# SCH_LED-Chaser_2025-12-03.net
KiCad netlist of a schematic drawn in EasyEDA
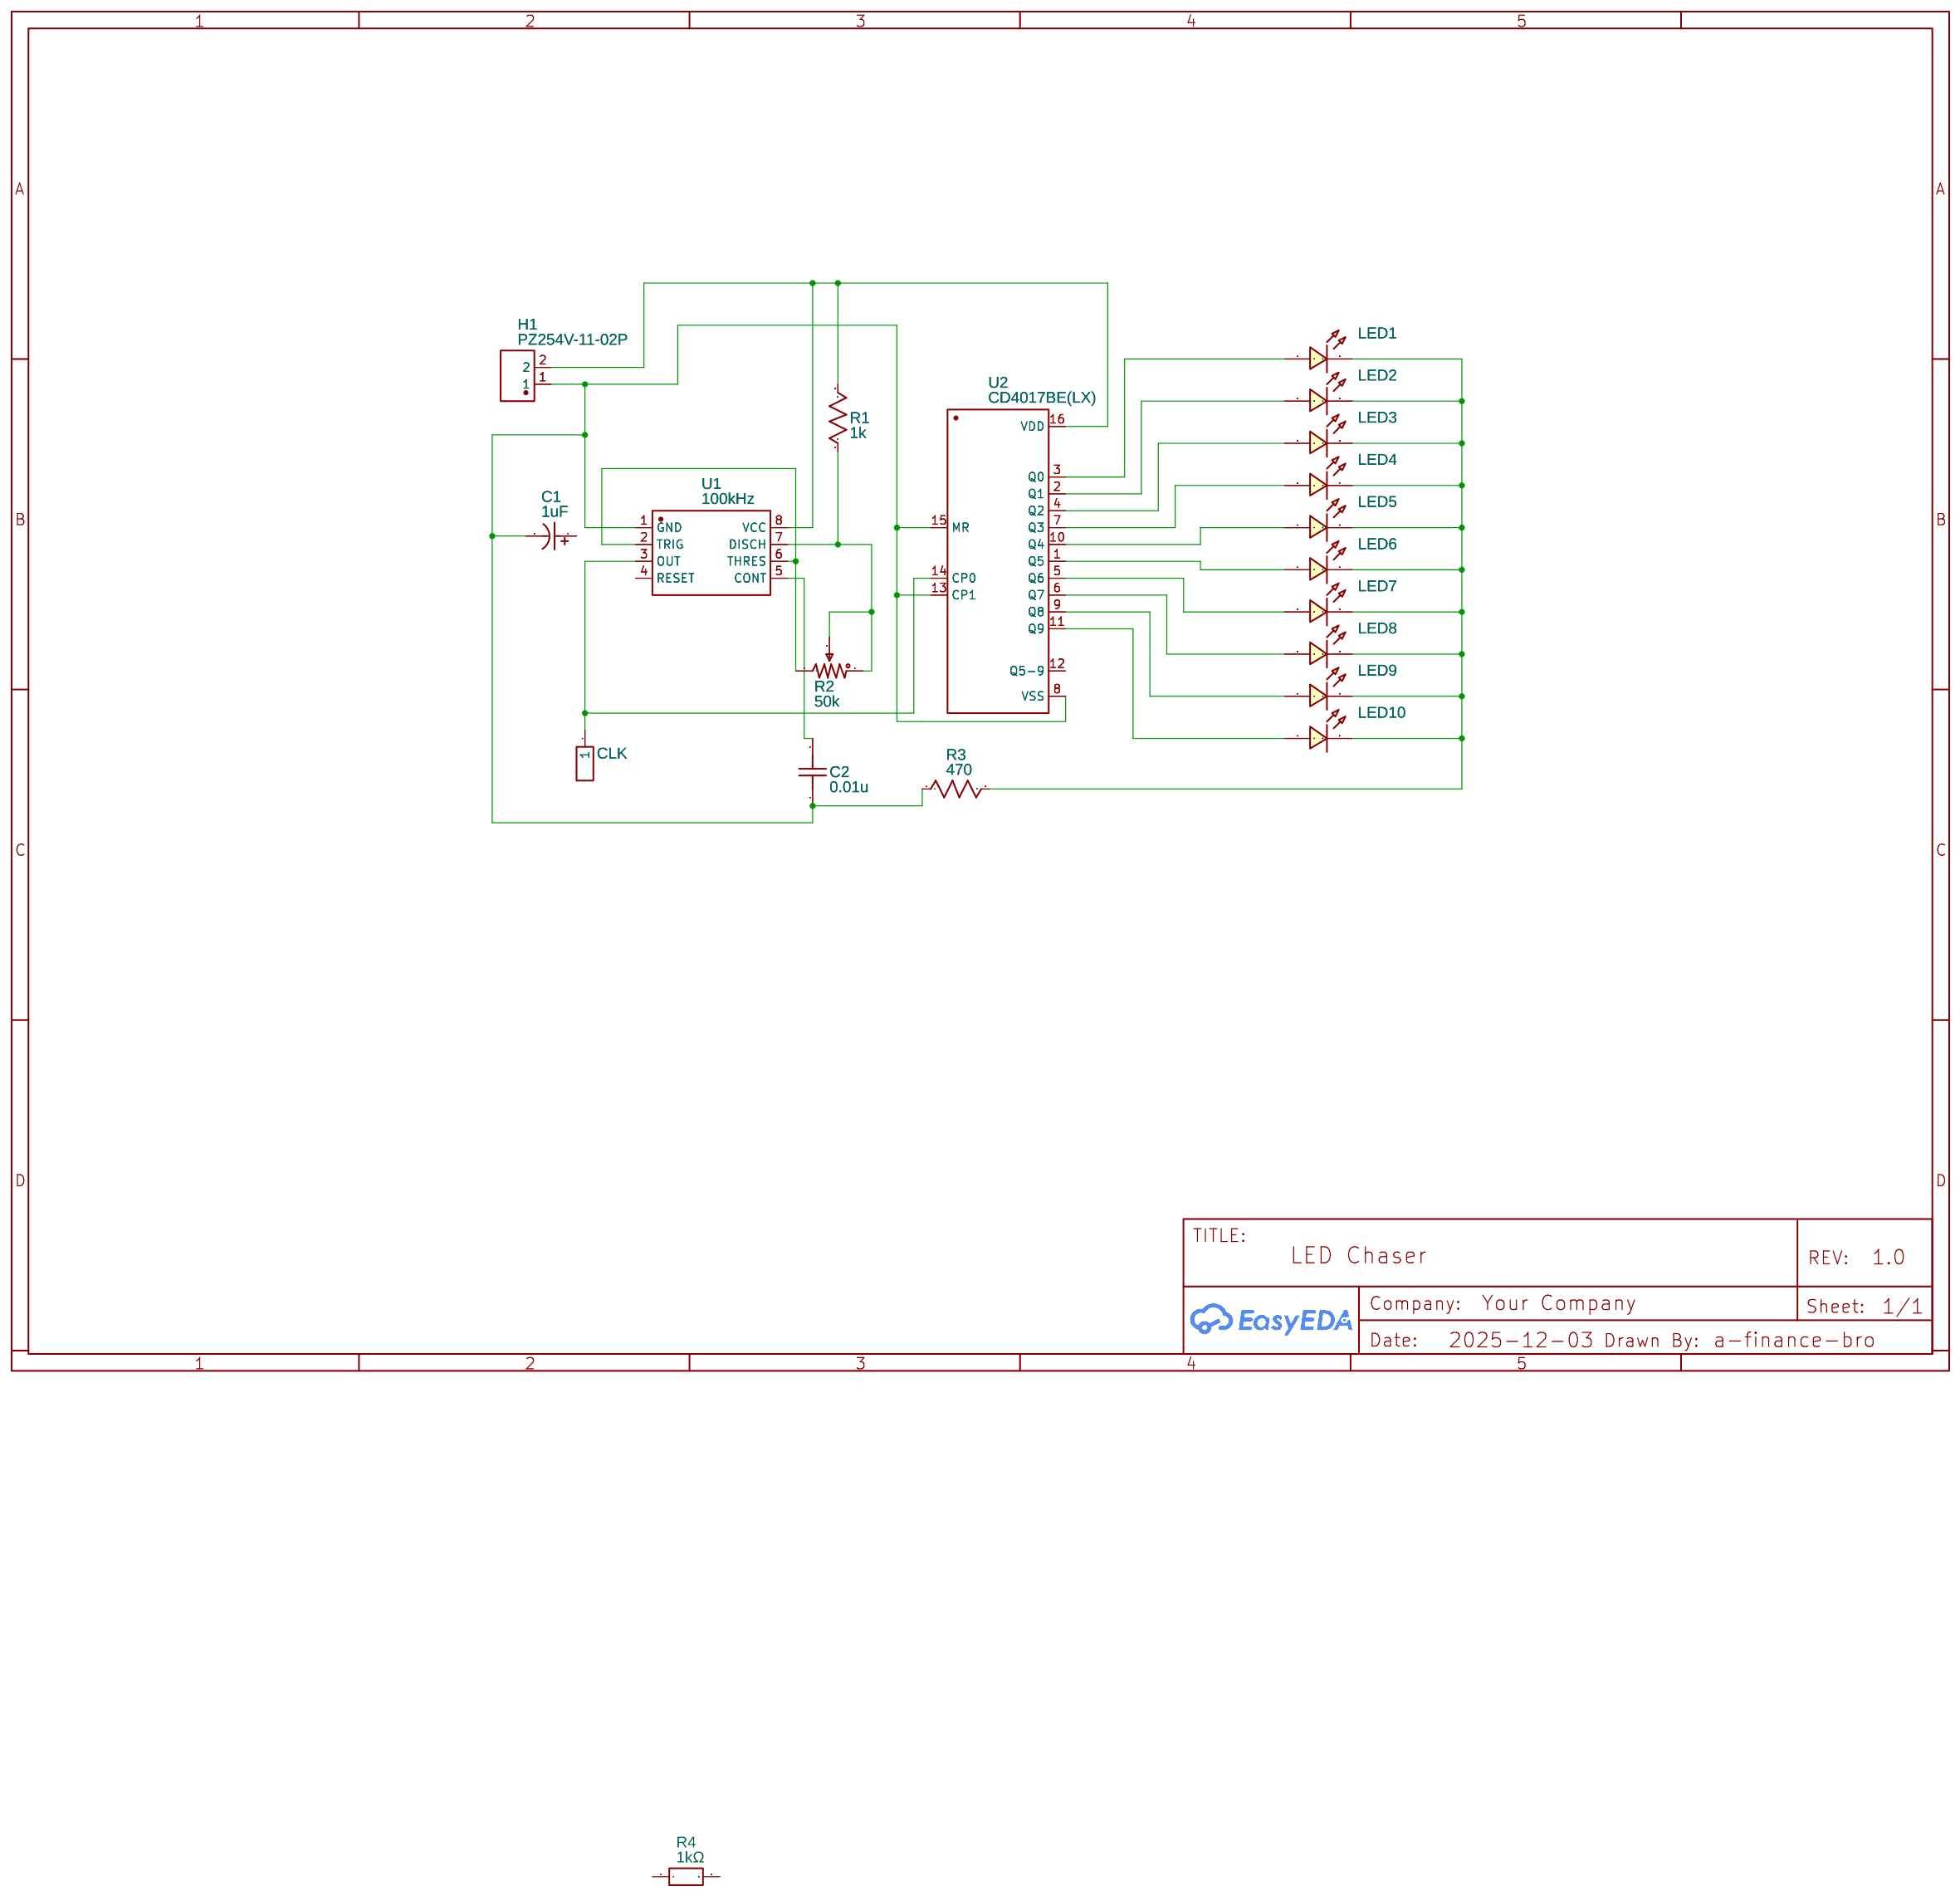
[diagram p0: schematic sheet]

(export (version "E")
  (design (tool "Eeschema 10.0.6"))
  (components
    (comp (ref "C1")
      (value "1uF")
      (fields (field (name "Manufacturer Part") "KF010M050C110A") (field (name "Manufacturer") "CapXon(丰宾)"))
      (libsource (lib "") (part "KF010M050C110A"))
    )
    (comp (ref "C2") (value "0.01u") (libsource (lib "") (part "C_0603_US")))
    (comp (ref "CLK") (value "HDR-M-2.54_1x1") (libsource (lib "") (part "HDR-M-2.54_1x1")))
    (comp (ref "H1")
      (value "PZ254V-11-02P")
      (fields (field (name "Manufacturer") "XFCN(兴飞)"))
      (libsource (lib "") (part "PZ254V-11-02P"))
    )
    (comp (ref "LED1")
      (value "LED-0603_R")
      (fields
        (field (name "Manufacturer Part") "19-217/R6C-AL1M2VY/3T")
        (field (name "Manufacturer") "EVERLIGHT(台湾亿光)")
      )
      (libsource (lib "") (part "LED-0603_R"))
    )
    (comp (ref "LED2")
      (value "LED-0603_R")
      (fields
        (field (name "Manufacturer Part") "19-217/R6C-AL1M2VY/3T")
        (field (name "Manufacturer") "EVERLIGHT(台湾亿光)")
      )
      (libsource (lib "") (part "LED-0603_R"))
    )
    (comp (ref "LED3")
      (value "LED-0603_R")
      (fields
        (field (name "Manufacturer Part") "19-217/R6C-AL1M2VY/3T")
        (field (name "Manufacturer") "EVERLIGHT(台湾亿光)")
      )
      (libsource (lib "") (part "LED-0603_R"))
    )
    (comp (ref "LED4")
      (value "LED-0603_R")
      (fields
        (field (name "Manufacturer Part") "19-217/R6C-AL1M2VY/3T")
        (field (name "Manufacturer") "EVERLIGHT(台湾亿光)")
      )
      (libsource (lib "") (part "LED-0603_R"))
    )
    (comp (ref "LED5")
      (value "LED-0603_R")
      (fields
        (field (name "Manufacturer Part") "19-217/R6C-AL1M2VY/3T")
        (field (name "Manufacturer") "EVERLIGHT(台湾亿光)")
      )
      (libsource (lib "") (part "LED-0603_R"))
    )
    (comp (ref "LED6")
      (value "LED-0603_R")
      (fields
        (field (name "Manufacturer Part") "19-217/R6C-AL1M2VY/3T")
        (field (name "Manufacturer") "EVERLIGHT(台湾亿光)")
      )
      (libsource (lib "") (part "LED-0603_R"))
    )
    (comp (ref "LED7")
      (value "LED-0603_R")
      (fields
        (field (name "Manufacturer Part") "19-217/R6C-AL1M2VY/3T")
        (field (name "Manufacturer") "EVERLIGHT(台湾亿光)")
      )
      (libsource (lib "") (part "LED-0603_R"))
    )
    (comp (ref "LED8")
      (value "LED-0603_R")
      (fields
        (field (name "Manufacturer Part") "19-217/R6C-AL1M2VY/3T")
        (field (name "Manufacturer") "EVERLIGHT(台湾亿光)")
      )
      (libsource (lib "") (part "LED-0603_R"))
    )
    (comp (ref "LED9")
      (value "LED-0603_R")
      (fields
        (field (name "Manufacturer Part") "19-217/R6C-AL1M2VY/3T")
        (field (name "Manufacturer") "EVERLIGHT(台湾亿光)")
      )
      (libsource (lib "") (part "LED-0603_R"))
    )
    (comp (ref "LED10")
      (value "LED-0603_R")
      (fields
        (field (name "Manufacturer Part") "19-217/R6C-AL1M2VY/3T")
        (field (name "Manufacturer") "EVERLIGHT(台湾亿光)")
      )
      (libsource (lib "") (part "LED-0603_R"))
    )
    (comp (ref "R1") (value "1k") (libsource (lib "") (part "R_0603_US")))
    (comp (ref "R2") (value "50k") (libsource (lib "") (part "R_3386P_US")))
    (comp (ref "R3") (value "470") (libsource (lib "") (part "R_0603_US_1")))
    (comp (ref "R4")
      (value "1kΩ")
      (fields (field (name "Manufacturer Part") "MF1/4W-1KΩ±1%T52") (field (name "Manufacturer") "华星机电"))
      (libsource (lib "") (part "MF1/4W-1KΩ±1%T52"))
    )
    (comp (ref "U1")
      (value "100kHz")
      (fields (field (name "Manufacturer Part") "NE555P") (field (name "Manufacturer") "TI(德州仪器)"))
      (libsource (lib "") (part "NE555P"))
    )
    (comp (ref "U2")
      (value "CD4017BE(LX)")
      (fields (field (name "Manufacturer") "LX(灵星芯微)"))
      (libsource (lib "") (part "CD4017BE(LX)"))
    )
  )
  (nets
    (net (code "1") (name "Net-(LED1-Pad2)") (class "Default")
      (node (ref "LED1") (pin "2") (pinfunction "2_2") (pintype "unspecified"))
      (node (ref "LED10") (pin "2") (pinfunction "2_2") (pintype "unspecified"))
      (node (ref "LED2") (pin "2") (pinfunction "2_2") (pintype "unspecified"))
      (node (ref "LED3") (pin "2") (pinfunction "2_2") (pintype "unspecified"))
      (node (ref "LED4") (pin "2") (pinfunction "2_2") (pintype "unspecified"))
      (node (ref "LED5") (pin "2") (pinfunction "2_2") (pintype "unspecified"))
      (node (ref "LED6") (pin "2") (pinfunction "2_2") (pintype "unspecified"))
      (node (ref "LED7") (pin "2") (pinfunction "2_2") (pintype "unspecified"))
      (node (ref "LED8") (pin "2") (pinfunction "2_2") (pintype "unspecified"))
      (node (ref "LED9") (pin "2") (pinfunction "2_2") (pintype "unspecified"))
      (node (ref "R3") (pin "2") (pinfunction "2_2") (pintype "unspecified"))
    )
    (net (code "2") (name "Net-(U1-CONT)") (class "Default")
      (node (ref "C2") (pin "2") (pinfunction "2_2") (pintype "unspecified"))
      (node (ref "U1") (pin "5") (pinfunction "CONT_5") (pintype "unspecified"))
    )
    (net (code "3") (name "Net-(U1-DISCH)") (class "Default")
      (node (ref "R1") (pin "1") (pinfunction "1_1") (pintype "unspecified"))
      (node (ref "R2") (pin "1") (pinfunction "1_1") (pintype "unspecified"))
      (node (ref "R2") (pin "2") (pinfunction "2_2") (pintype "unspecified"))
      (node (ref "U1") (pin "7") (pinfunction "DISCH_7") (pintype "unspecified"))
    )
    (net (code "4") (name "Net-(U1-GND)") (class "Default")
      (node (ref "C1") (pin "2") (pinfunction "2_2") (pintype "input"))
      (node (ref "C2") (pin "1") (pinfunction "1_1") (pintype "unspecified"))
      (node (ref "H1") (pin "1") (pinfunction "1_1") (pintype "unspecified"))
      (node (ref "R3") (pin "1") (pinfunction "1_1") (pintype "unspecified"))
      (node (ref "U1") (pin "1") (pinfunction "GND_1") (pintype "unspecified"))
      (node (ref "U2") (pin "13") (pinfunction "CP1_13") (pintype "unspecified"))
      (node (ref "U2") (pin "15") (pinfunction "MR_15") (pintype "unspecified"))
      (node (ref "U2") (pin "8") (pinfunction "VSS_8") (pintype "unspecified"))
    )
    (net (code "5") (name "Net-(U1-OUT)") (class "Default")
      (node (ref "CLK") (pin "1") (pinfunction "1_1") (pintype "input"))
      (node (ref "U1") (pin "3") (pinfunction "OUT_3") (pintype "unspecified"))
      (node (ref "U2") (pin "14") (pinfunction "CP0_14") (pintype "unspecified"))
    )
    (net (code "6") (name "Net-(U1-THRES)") (class "Default")
      (node (ref "R2") (pin "3") (pinfunction "3_3") (pintype "unspecified"))
      (node (ref "U1") (pin "2") (pinfunction "TRIG_2") (pintype "unspecified"))
      (node (ref "U1") (pin "6") (pinfunction "THRES_6") (pintype "unspecified"))
    )
    (net (code "7") (name "Net-(U1-VCC)") (class "Default")
      (node (ref "H1") (pin "2") (pinfunction "2_2") (pintype "unspecified"))
      (node (ref "R1") (pin "2") (pinfunction "2_2") (pintype "unspecified"))
      (node (ref "U1") (pin "8") (pinfunction "VCC_8") (pintype "unspecified"))
      (node (ref "U2") (pin "16") (pinfunction "VDD_16") (pintype "unspecified"))
    )
    (net (code "8") (name "Net-(U2-Q0)") (class "Default")
      (node (ref "LED1") (pin "1") (pinfunction "1_1") (pintype "unspecified"))
      (node (ref "U2") (pin "3") (pinfunction "Q0_3") (pintype "unspecified"))
    )
    (net (code "9") (name "Net-(U2-Q1)") (class "Default")
      (node (ref "LED2") (pin "1") (pinfunction "1_1") (pintype "unspecified"))
      (node (ref "U2") (pin "2") (pinfunction "Q1_2") (pintype "unspecified"))
    )
    (net (code "10") (name "Net-(U2-Q2)") (class "Default")
      (node (ref "LED3") (pin "1") (pinfunction "1_1") (pintype "unspecified"))
      (node (ref "U2") (pin "4") (pinfunction "Q2_4") (pintype "unspecified"))
    )
    (net (code "11") (name "Net-(U2-Q3)") (class "Default")
      (node (ref "LED4") (pin "1") (pinfunction "1_1") (pintype "unspecified"))
      (node (ref "U2") (pin "7") (pinfunction "Q3_7") (pintype "unspecified"))
    )
    (net (code "12") (name "Net-(U2-Q4)") (class "Default")
      (node (ref "LED5") (pin "1") (pinfunction "1_1") (pintype "unspecified"))
      (node (ref "U2") (pin "10") (pinfunction "Q4_10") (pintype "unspecified"))
    )
    (net (code "13") (name "Net-(U2-Q5)") (class "Default")
      (node (ref "LED6") (pin "1") (pinfunction "1_1") (pintype "unspecified"))
      (node (ref "U2") (pin "1") (pinfunction "Q5_1") (pintype "unspecified"))
    )
    (net (code "14") (name "Net-(U2-Q6)") (class "Default")
      (node (ref "LED7") (pin "1") (pinfunction "1_1") (pintype "unspecified"))
      (node (ref "U2") (pin "5") (pinfunction "Q6_5") (pintype "unspecified"))
    )
    (net (code "15") (name "Net-(U2-Q7)") (class "Default")
      (node (ref "LED8") (pin "1") (pinfunction "1_1") (pintype "unspecified"))
      (node (ref "U2") (pin "6") (pinfunction "Q7_6") (pintype "unspecified"))
    )
    (net (code "16") (name "Net-(U2-Q8)") (class "Default")
      (node (ref "LED9") (pin "1") (pinfunction "1_1") (pintype "unspecified"))
      (node (ref "U2") (pin "9") (pinfunction "Q8_9") (pintype "unspecified"))
    )
    (net (code "17") (name "Net-(U2-Q9)") (class "Default")
      (node (ref "LED10") (pin "1") (pinfunction "1_1") (pintype "unspecified"))
      (node (ref "U2") (pin "11") (pinfunction "Q9_11") (pintype "unspecified"))
    )
    (net (code "18") (name "unconnected-(C1-Pad1)") (class "Default")
      (node (ref "C1") (pin "1") (pinfunction "1_1") (pintype "input"))
    )
    (net (code "19") (name "unconnected-(R4-Pad1)") (class "Default")
      (node (ref "R4") (pin "1") (pinfunction "1_1") (pintype "unspecified"))
    )
    (net (code "20") (name "unconnected-(R4-Pad2)") (class "Default")
      (node (ref "R4") (pin "2") (pinfunction "2_2") (pintype "unspecified"))
    )
    (net (code "21") (name "unconnected-(U1-RESET-Pad4)") (class "Default")
      (node (ref "U1") (pin "4") (pinfunction "RESET_4") (pintype "unspecified"))
    )
    (net (code "22") (name "unconnected-(U2-Q5-9-Pad12)") (class "Default")
      (node (ref "U2") (pin "12") (pinfunction "Q5-9_12") (pintype "unspecified"))
    )
  )
)
